# XCOMBO_35.net
KiCad netlist of a schematic drawn in EAGLE
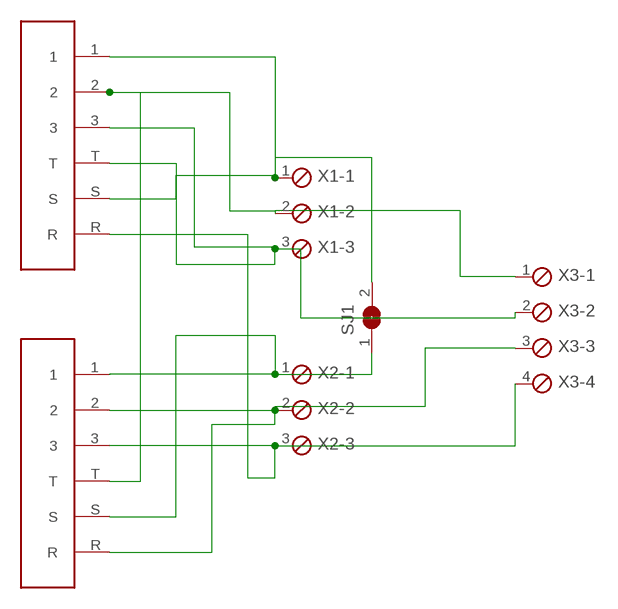
[diagram p0: schematic, sheet 1]

(export (version "E")
  (design (tool "Eeschema 10.0.6"))
  (components
    (comp (ref "SJ1") (value "SJ") (footprint "eagle-import:SJ") (libsource (lib "eagle-import") (part "SJ")))
    (comp (ref "U$1")
      (value "XLRCOMBO")
      (footprint "eagle-import:NCJ6FI-S-0")
      (libsource (lib "eagle-import") (part "XLRCOMBO"))
    )
    (comp (ref "U$2")
      (value "XLRCOMBO")
      (footprint "eagle-import:NCJ6FI-S-0")
      (libsource (lib "eagle-import") (part "XLRCOMBO"))
    )
    (comp (ref "X1")
      (value "MPT3")
      (footprint "eagle-import:3POL254")
      (libsource (lib "eagle-import") (part "MPT3"))
    )
    (comp (ref "X2")
      (value "MPT3")
      (footprint "eagle-import:3POL254")
      (libsource (lib "eagle-import") (part "MPT3"))
    )
    (comp (ref "X3")
      (value "MPT4")
      (footprint "eagle-import:4POL254")
      (libsource (lib "eagle-import") (part "MPT4"))
    )
  )
  (nets
    (net (code "1") (name "Net-(SJ1-Pad1)") (class "Default")
      (node (ref "SJ1") (pin "1") (pinfunction "1_1") (pintype "passive"))
      (node (ref "U$1") (pin "1") (pinfunction "1_1") (pintype "bidirectional"))
      (node (ref "U$1") (pin "S") (pinfunction "S_S") (pintype "bidirectional"))
      (node (ref "X2") (pin "1") (pinfunction "1_1") (pintype "passive"))
    )
    (net (code "2") (name "Net-(SJ1-Pad2)") (class "Default")
      (node (ref "SJ1") (pin "2") (pinfunction "2_2") (pintype "passive"))
      (node (ref "U$2") (pin "1") (pinfunction "1_1") (pintype "bidirectional"))
      (node (ref "U$2") (pin "S") (pinfunction "S_S") (pintype "bidirectional"))
      (node (ref "X1") (pin "1") (pinfunction "1_1") (pintype "passive"))
    )
    (net (code "3") (name "Net-(X1B-1)") (class "Default")
      (node (ref "U$1") (pin "T") (pinfunction "T_T") (pintype "bidirectional"))
      (node (ref "U$2") (pin "2") (pinfunction "2_2") (pintype "bidirectional"))
      (node (ref "X1") (pin "2") (pinfunction "1_2") (pintype "passive"))
      (node (ref "X3") (pin "1") (pinfunction "1_1") (pintype "passive"))
    )
    (net (code "4") (name "Net-(X1C-1)") (class "Default")
      (node (ref "U$2") (pin "3") (pinfunction "3_3") (pintype "bidirectional"))
      (node (ref "U$2") (pin "T") (pinfunction "T_T") (pintype "bidirectional"))
      (node (ref "X1") (pin "3") (pinfunction "1_3") (pintype "passive"))
      (node (ref "X3") (pin "2") (pinfunction "1_2") (pintype "passive"))
    )
    (net (code "5") (name "Net-(X2B-1)") (class "Default")
      (node (ref "U$1") (pin "2") (pinfunction "2_2") (pintype "bidirectional"))
      (node (ref "U$1") (pin "R") (pinfunction "R_R") (pintype "bidirectional"))
      (node (ref "X2") (pin "2") (pinfunction "1_2") (pintype "passive"))
      (node (ref "X3") (pin "3") (pinfunction "1_3") (pintype "passive"))
    )
    (net (code "6") (name "Net-(X2C-1)") (class "Default")
      (node (ref "U$1") (pin "3") (pinfunction "3_3") (pintype "bidirectional"))
      (node (ref "U$2") (pin "R") (pinfunction "R_R") (pintype "bidirectional"))
      (node (ref "X2") (pin "3") (pinfunction "1_3") (pintype "passive"))
      (node (ref "X3") (pin "4") (pinfunction "1_4") (pintype "passive"))
    )
  )
)
